# CarGeoLogger.net
KiCad netlist of a schematic drawn in Altium Designer
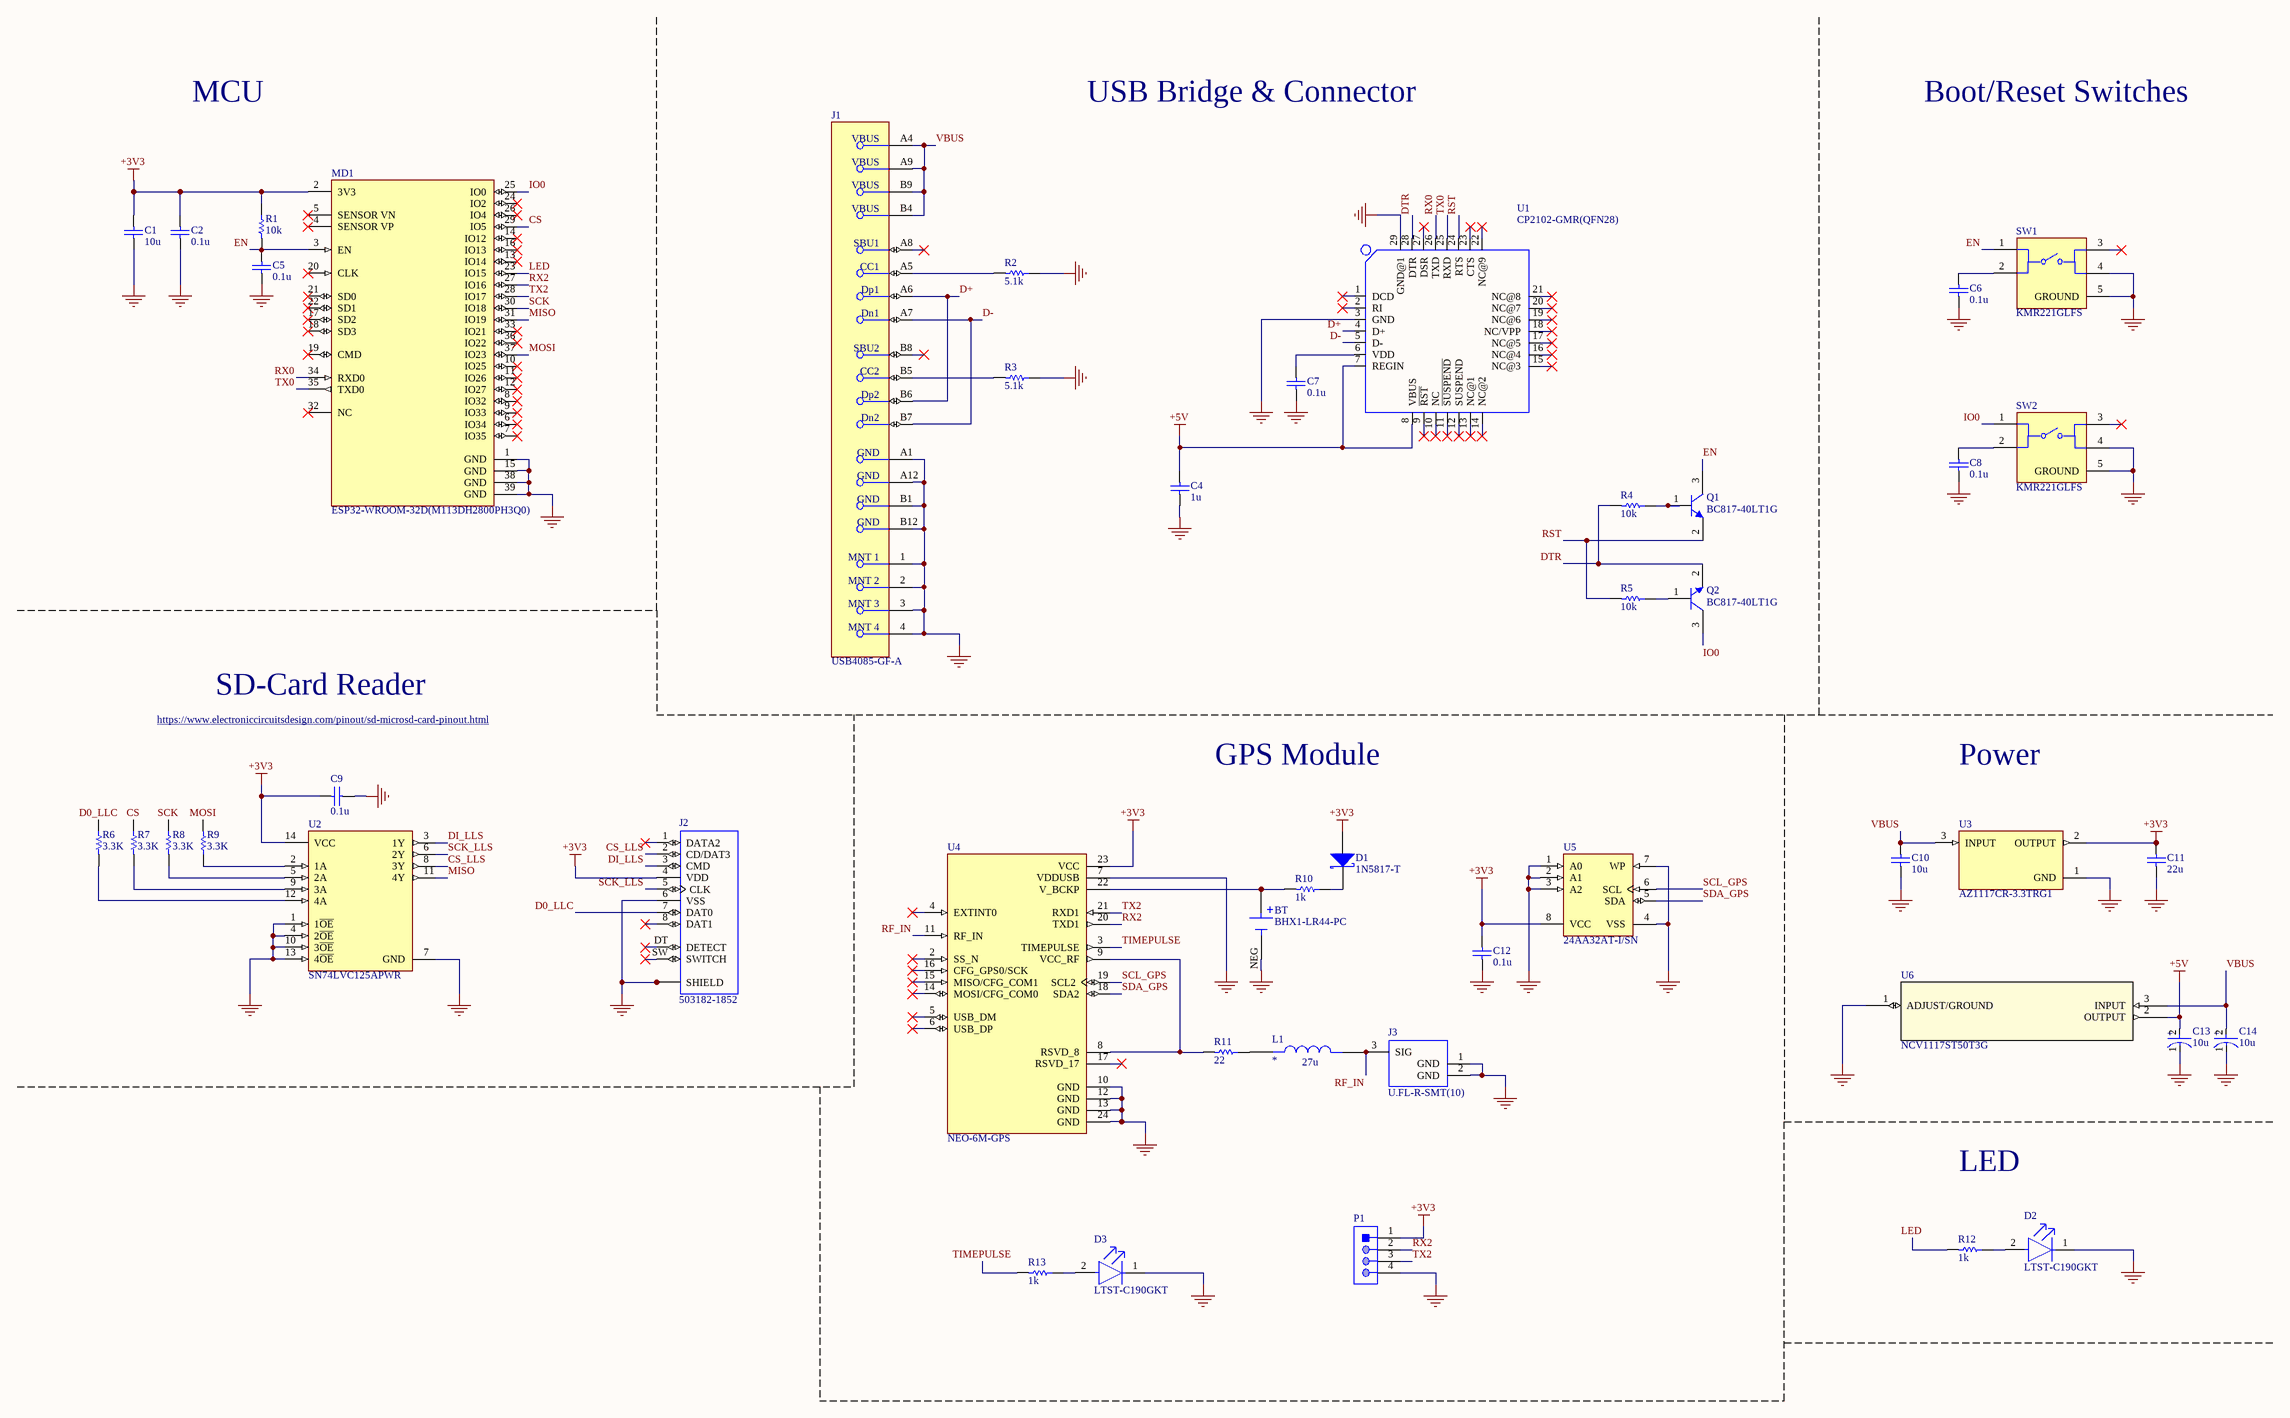
[diagram p0: CarGeoLogger.SchDoc]

(export (version "E")
  (design (tool "Eeschema 10.0.6"))
  (components
    (comp (ref "BT")
      (value "BHX1-LR44-PC")
      (footprint "BAT_BHX1-LR44-PC")
      (description "Battery Retainer Coin, 12.0mm 1 Cell PC Pin")
      (fields (field (name "MF") "MPD"))
      (libsource (lib "Kendrick Nguyen") (part "BHX1-LR44-PC"))
    )
    (comp (ref "C1")
      (value "10u")
      (footprint "CAPC1608X90X35ML10T15")
      (description "Chip Capacitor, 0603 (1608 Metric)")
      (fields (field (name "MANUFACTURER") "Murata"))
      (libsource (lib "Altium Content Vault") (part "CAP-NP-2"))
    )
    (comp (ref "C2")
      (value "0.1u")
      (footprint "CAPC1608X90X35ML10T15")
      (description "Chip Capacitor, 0603 (1608 Metric)")
      (fields (field (name "MANUFACTURER") "Murata"))
      (libsource (lib "Altium Content Vault") (part "CAP-NP-2"))
    )
    (comp (ref "C4")
      (value "1u")
      (footprint "CAPC1608X90X35ML10T15")
      (description "Chip Capacitor, 0603 (1608 Metric)")
      (fields (field (name "MANUFACTURER") "Murata"))
      (libsource (lib "Altium Content Vault") (part "CAP-NP-2"))
    )
    (comp (ref "C5")
      (value "0.1u")
      (footprint "CAPC1608X90X35ML10T15")
      (description "Chip Capacitor, 0603 (1608 Metric)")
      (fields (field (name "MANUFACTURER") "Murata"))
      (libsource (lib "Altium Content Vault") (part "CAP-NP-2"))
    )
    (comp (ref "C6")
      (value "0.1u")
      (footprint "CAPC1608X90X35ML10T15")
      (description "Chip Capacitor, 0603 (1608 Metric)")
      (fields (field (name "MANUFACTURER") "Murata"))
      (libsource (lib "Altium Content Vault") (part "CAP-NP-2"))
    )
    (comp (ref "C7")
      (value "0.1u")
      (footprint "CAPC1608X90X35ML10T15")
      (description "Chip Capacitor, 0603 (1608 Metric)")
      (fields (field (name "MANUFACTURER") "Murata"))
      (libsource (lib "Altium Content Vault") (part "CAP-NP-2"))
    )
    (comp (ref "C8")
      (value "0.1u")
      (footprint "CAPC1608X90X35ML10T15")
      (description "Chip Capacitor, 0603 (1608 Metric)")
      (fields (field (name "MANUFACTURER") "Murata"))
      (libsource (lib "Altium Content Vault") (part "CAP-NP-2"))
    )
    (comp (ref "C9")
      (value "0.1u")
      (footprint "CAPC1608X90X35ML10T15")
      (description "Chip Capacitor, 0603 (1608 Metric)")
      (fields (field (name "MANUFACTURER") "Murata"))
      (libsource (lib "Altium Content Vault") (part "CAP-NP-2"))
    )
    (comp (ref "C10")
      (value "10u")
      (footprint "CAPC1608X90X35ML10T15")
      (description "Chip Capacitor, 0603 (1608 Metric)")
      (fields (field (name "MANUFACTURER") "Murata"))
      (libsource (lib "Altium Content Vault") (part "CAP-NP-2"))
    )
    (comp (ref "C11")
      (value "22u")
      (footprint "CAPC1608X90X35ML10T15")
      (description "Chip Capacitor, 0603 (1608 Metric), F381A106MMAAH1")
      (fields (field (name "MANUFACTURER") "Murata"))
      (libsource (lib "Altium Content Vault") (part "CAP-NP-2"))
    )
    (comp (ref "C12")
      (value "0.1u")
      (footprint "CAPC1608X90X35ML10T15")
      (description "Chip Capacitor, 0603 (1608 Metric)")
      (fields (field (name "MANUFACTURER") "Murata"))
      (libsource (lib "Altium Content Vault") (part "CAP-NP-2"))
    )
    (comp (ref "C13")
      (value "10u")
      (footprint "FP-F38M-MFG")
      (description "CAP TANT POLY 10UF 10V SMD")
      (fields
        (field (name "MANUFACTURER PART NUMBER") "F381A106MMAAH1")
        (field (name "OCTOPART") "https://octopart.com/f381a106mmaah1-avx-67040376")
      )
      (libsource (lib "Altium Content Vault") (part "cf48714ba7e38822c1575c7ec0b6d1f"))
    )
    (comp (ref "C14")
      (value "10u")
      (footprint "FP-F38M-MFG")
      (description "CAP TANT POLY 10UF 10V SMD")
      (fields
        (field (name "MANUFACTURER PART NUMBER") "F381A106MMAAH1")
        (field (name "OCTOPART") "https://octopart.com/f381a106mmaah1-avx-67040376")
      )
      (libsource (lib "Altium Content Vault") (part "cf48714ba7e38822c1575c7ec0b6d1f"))
    )
    (comp (ref "D1")
      (value "1N5817-T")
      (footprint "DIOD-DO-41-P-2")
      (description "Schottky Barrier Rectifier, 1 A, 20 V, -65 to 125 degC, 2-Pin DO-41, RoHS, Tape and Reel")
      (fields (field (name "MANUFACTURER") "DiodesIncorporated"))
      (libsource (lib "Altium Content Vault") (part "DSKY-AK-2"))
    )
    (comp (ref "D2")
      (value "LTST-C190GKT")
      (footprint "FP-LTST-C190GKT-MFG")
      (description "LED GREEN CLEAR CHIP SMD")
      (fields (field (name "VOLTAGE") "2V"))
      (libsource (lib "Altium Content Vault") (part "8706943c75ba83719d021d2fdc84c58"))
    )
    (comp (ref "D3")
      (value "LTST-C190GKT")
      (footprint "FP-LTST-C190GKT-MFG")
      (description "LED GREEN CLEAR CHIP SMD")
      (fields (field (name "VOLTAGE") "2V"))
      (libsource (lib "Altium Content Vault") (part "8706943c75ba83719d021d2fdc84c58"))
    )
    (comp (ref "J1")
      (value "USB4085-GF-A")
      (footprint "FP-USB4085-GF-A-MFG")
      (description "CONN RCPT USB2.0 TYPE C 24POS RA")
      (libsource (lib "Altium Content Vault") (part "10fa745527c8b974685cbca3c197132"))
    )
    (comp (ref "J2")
      (value "503182-1852")
      (footprint "MOLEX_503182-1852")
      (description "Conn Micro SD Card M 8 POS 1.09mm Solder RA SMD Embossed T/R 0.5A/Contact")
      (libsource (lib "Kendrick Nguyen") (part "503182-1852"))
    )
    (comp (ref "J3")
      (value "U.FL-R-SMT(10)")
      (footprint "HRS-U.FL-R-SMT_V")
      (fields (field (name "MANUFACTURER") "Hirose Electric"))
      (libsource (lib "Kendrick Nguyen") (part "HRS-U.FL-R-SMT-3"))
    )
    (comp (ref "L1")
      (value "27u")
      (footprint "INDC1608X95N")
      (description "Ind RF Chip Shielded Multi-Layer 27uH 10% 1MHz 20Q-Factor Ferrite 2mA 0603 Punched Paper T/R")
      (fields
        (field (name "ALTIUM_VALUE") "*")
        (field (name "MF") "TDK")
        (field (name "MP") "MLF1608C270KTD00")
      )
      (libsource (lib "Kendrick Nguyen") (part "MLF1608C270KTD00"))
    )
    (comp (ref "MD1")
      (value "ESP32-WROOM-32D(M113DH2800PH3Q0)")
      (footprint "FP-ESP32-WROOM-32D_M113DH-MFG")
      (description "RX TXRX MOD WIFI TRACE ANT SMD")
      (libsource (lib "Altium Content Vault") (part "68cda691c5ebc01e0f685e2e9d3fb9b"))
    )
    (comp (ref "P1")
      (value "~")
      (footprint "61300411121")
      (description "THT Vertical Pin Header WR-PHD, Pitch 2.54 mm, Single Row, 4 pins")
      (fields
        (field (name "MANUFACTURER") "Wurth Elektronik")
        (field (name "PART NUMBER") "61300411121")
        (field (name "PUBLISHER") "WurthElektronik")
      )
      (libsource (lib "Altium Content Vault") (part "WE-CN-1P-M-R4"))
    )
    (comp (ref "Q1")
      (value "BC817-40LT1G")
      (footprint "ONSC-SOT-23-3-318-08_V")
      (description "General Purpose Transistor, NPN Silicon, 3-Pin SOT-23, Pb-Free, Tape and Reel")
      (fields (field (name "MANUFACTURER") "On Semiconductor"))
      (libsource (lib "Altium Content Vault") (part "ONSC-NPN-B1E2C3-3"))
    )
    (comp (ref "Q2")
      (value "BC817-40LT1G")
      (footprint "ONSC-SOT-23-3-318-08_V")
      (description "General Purpose Transistor, NPN Silicon, 3-Pin SOT-23, Pb-Free, Tape and Reel")
      (fields (field (name "MANUFACTURER") "On Semiconductor"))
      (libsource (lib "Altium Content Vault") (part "ONSC-NPN-B1E2C3-3"))
    )
    (comp (ref "R1")
      (value "10k")
      (footprint "RESC1609X50X30NL8T20")
      (description "Chip Resistor, 0603 (1608 Metric)")
      (fields (field (name "MANUFACTURER") "Vishay Semiconductor"))
      (libsource (lib "Altium Content Vault") (part "RES-2"))
    )
    (comp (ref "R2")
      (value "5.1k")
      (footprint "RESC1609X50X30NL8T20")
      (description "Chip Resistor, 0603 (1608 Metric)")
      (fields (field (name "MANUFACTURER") "Vishay Semiconductor"))
      (libsource (lib "Altium Content Vault") (part "RES-2"))
    )
    (comp (ref "R3")
      (value "5.1k")
      (footprint "RESC1609X50X30NL8T20")
      (description "Chip Resistor, 0603 (1608 Metric)")
      (fields (field (name "MANUFACTURER") "Vishay Semiconductor"))
      (libsource (lib "Altium Content Vault") (part "RES-2"))
    )
    (comp (ref "R4")
      (value "10k")
      (footprint "RESC1609X50X30NL8T20")
      (description "Chip Resistor, 0603 (1608 Metric)")
      (fields (field (name "MANUFACTURER") "Vishay Semiconductor"))
      (libsource (lib "Altium Content Vault") (part "RES-2"))
    )
    (comp (ref "R5")
      (value "10k")
      (footprint "RESC1609X50X30NL8T20")
      (description "Chip Resistor, 0603 (1608 Metric)")
      (fields (field (name "MANUFACTURER") "Vishay Semiconductor"))
      (libsource (lib "Altium Content Vault") (part "RES-2"))
    )
    (comp (ref "R6")
      (value "3.3K")
      (footprint "RESC1609X50X30NL8T20")
      (description "Chip Resistor, 0603 (1608 Metric)")
      (fields (field (name "MANUFACTURER") "Vishay Semiconductor"))
      (libsource (lib "Altium Content Vault") (part "RES-2"))
    )
    (comp (ref "R7")
      (value "3.3K")
      (footprint "RESC1609X50X30NL8T20")
      (description "Chip Resistor, 0603 (1608 Metric)")
      (fields (field (name "MANUFACTURER") "Vishay Semiconductor"))
      (libsource (lib "Altium Content Vault") (part "RES-2"))
    )
    (comp (ref "R8")
      (value "3.3K")
      (footprint "RESC1609X50X30NL8T20")
      (description "Chip Resistor, 0603 (1608 Metric)")
      (fields (field (name "MANUFACTURER") "Vishay Semiconductor"))
      (libsource (lib "Altium Content Vault") (part "RES-2"))
    )
    (comp (ref "R9")
      (value "3.3K")
      (footprint "RESC1609X50X30NL8T20")
      (description "Chip Resistor, 0603 (1608 Metric)")
      (fields (field (name "MANUFACTURER") "Vishay Semiconductor"))
      (libsource (lib "Altium Content Vault") (part "RES-2"))
    )
    (comp (ref "R10")
      (value "1k")
      (footprint "RESC1609X50X30NL8T20")
      (description "Chip Resistor, 0603 (1608 Metric)")
      (fields (field (name "MANUFACTURER") "Vishay Semiconductor"))
      (libsource (lib "Altium Content Vault") (part "RES-2"))
    )
    (comp (ref "R11")
      (value "22")
      (footprint "RESC1609X50X30NL8T20")
      (description "Chip Resistor, 0603 (1608 Metric)")
      (fields (field (name "MANUFACTURER") "Vishay Semiconductor"))
      (libsource (lib "Altium Content Vault") (part "RES-2"))
    )
    (comp (ref "R12")
      (value "1k")
      (footprint "RESC1609X50X30NL8T20")
      (description "Chip Resistor, 0603 (1608 Metric)")
      (fields (field (name "MANUFACTURER") "Vishay Semiconductor"))
      (libsource (lib "Altium Content Vault") (part "RES-2"))
    )
    (comp (ref "R13")
      (value "1k")
      (footprint "RESC1609X50X30NL8T20")
      (description "Chip Resistor, 0603 (1608 Metric)")
      (fields (field (name "MANUFACTURER") "Vishay Semiconductor"))
      (libsource (lib "Altium Content Vault") (part "RES-2"))
    )
    (comp (ref "SW1")
      (value "KMR221GLFS")
      (footprint "FP-KMR221GLFS-MFG")
      (description "SWITCH TACTILE SPST-NO 0.05A 32V")
      (libsource (lib "Altium Content Vault") (part "067e1cfe0b8977aedbfee7786663f4c"))
    )
    (comp (ref "SW2")
      (value "KMR221GLFS")
      (footprint "FP-KMR221GLFS-MFG")
      (description "SWITCH TACTILE SPST-NO 0.05A 32V")
      (libsource (lib "Altium Content Vault") (part "067e1cfe0b8977aedbfee7786663f4c"))
    )
    (comp (ref "U1")
      (value "CP2102-GMR(QFN28)")
      (footprint "QFN28G_0.5-5X5MM")
      (description "USB Bridge, USB to UART USB 2.0 UART Interface 28-QFN _5x5_")
      (fields (field (name "MP") "CP2102-GMR") (field (name "MF") "Silicon"))
      (libsource (lib "Kendrick Nguyen") (part "INTERFACE-CP2102-GMR(QFN28)"))
    )
    (comp (ref "U2")
      (value "SN74LVC125APWR")
      (footprint "FP-PW0014A-IPC_B")
      (description "IC BUF NON-INVERT 3.6V 14TSSOP")
      (libsource (lib "Altium Content Vault") (part "0c185306b27c65c3e4a0d950f37c68a"))
    )
    (comp (ref "U3")
      (value "AZ1117CR-3.3TRG1")
      (footprint "FP-SOT89-MFG")
      (description "IC REG LINEAR 3.3V 800MA SOT89")
      (fields
        (field (name "OCTOPART") "https://octopart.com/az1117cr-3.3trg1-diodes+inc.-30954805")
        (field (name "MANUFACTURER") "Diodes Inc.")
      )
      (libsource (lib "Altium Content Vault") (part "80dc4d5e0c5bf011f486f511683fde3"))
    )
    (comp (ref "U4")
      (value "NEO-6M-GPS")
      (footprint "XCVR_NEO-6M-GPS")
      (description "SMD GPS Module")
      (libsource (lib "Kendrick Nguyen") (part "NEO-6M-GPS"))
    )
    (comp (ref "U5")
      (value "24AA32AT-I/SN")
      (footprint "SOIC-SN8_L")
      (description "32Kbit, 400kHz, 1.7V, I2C Serial EEPROM, 8-Pin SOIC 150mil, Industrial Temperature, Tape and Reel")
      (libsource (lib "Altium Content Vault") (part "MEM-SEEPROM-34AA02-IL8"))
    )
    (comp (ref "U6")
      (value "NCV1117ST50T3G")
      (footprint "SOT223-3_ONS")
      (description "No Description Available")
      (fields (field (name "COPYRIGHT") "Copyright (C) 2022 Ultra Librarian. All rights reserved."))
      (libsource (lib "Kendrick Nguyen") (part "NCV1117ST50T3G"))
    )
  )
  (nets
    (net (code "1") (name "+3V3") (class "Default")
      (node (ref "C1") (pin "2") (pinfunction "2_2") (pintype "passive"))
      (node (ref "C11") (pin "2") (pinfunction "2_2") (pintype "passive"))
      (node (ref "C12") (pin "2") (pinfunction "2_2") (pintype "passive"))
      (node (ref "C2") (pin "2") (pinfunction "2_2") (pintype "passive"))
      (node (ref "C9") (pin "2") (pinfunction "2_2") (pintype "passive"))
      (node (ref "D1") (pin "1") (pinfunction "A_1") (pintype "passive"))
      (node (ref "J2") (pin "4") (pinfunction "VDD_4") (pintype "power_in"))
      (node (ref "MD1") (pin "2") (pinfunction "3V3_2") (pintype "power_in"))
      (node (ref "P1") (pin "1") (pinfunction "1_1") (pintype "passive"))
      (node (ref "R1") (pin "1") (pinfunction "1_1") (pintype "passive"))
      (node (ref "U2") (pin "14") (pinfunction "VCC_14") (pintype "power_in"))
      (node (ref "U3") (pin "2") (pinfunction "OUTPUT_2") (pintype "output"))
      (node (ref "U4") (pin "23") (pinfunction "VCC_23") (pintype "power_in"))
      (node (ref "U5") (pin "8") (pinfunction "VCC_8") (pintype "power_in"))
    )
    (net (code "2") (name "+5V") (class "Default")
      (node (ref "C13") (pin "2") (pinfunction "A_2") (pintype "passive"))
      (node (ref "C4") (pin "2") (pinfunction "2_2") (pintype "passive"))
      (node (ref "U1") (pin "7") (pinfunction "REGIN_7") (pintype "bidirectional"))
      (node (ref "U1") (pin "8") (pinfunction "VBUS_8") (pintype "bidirectional"))
      (node (ref "U6") (pin "2") (pinfunction "OUTPUT_2") (pintype "output"))
    )
    (net (code "3") (name "/CS") (class "Default")
      (node (ref "MD1") (pin "29") (pinfunction "IO5_29") (pintype "bidirectional"))
      (node (ref "R7") (pin "1") (pinfunction "1_1") (pintype "passive"))
    )
    (net (code "4") (name "/CS_LLS") (class "Default")
      (node (ref "J2") (pin "2") (pinfunction "CD/DAT3_2") (pintype "bidirectional"))
      (node (ref "U2") (pin "8") (pinfunction "3Y_8") (pintype "output"))
    )
    (net (code "5") (name "/D+") (class "Default")
      (node (ref "J1") (pin "A6") (pinfunction "Dp1_A6") (pintype "bidirectional"))
      (node (ref "J1") (pin "B6") (pinfunction "Dp2_B6") (pintype "bidirectional"))
      (node (ref "U1") (pin "4") (pinfunction "D+_4") (pintype "bidirectional"))
    )
    (net (code "6") (name "/D-") (class "Default")
      (node (ref "J1") (pin "A7") (pinfunction "Dn1_A7") (pintype "bidirectional"))
      (node (ref "J1") (pin "B7") (pinfunction "Dn2_B7") (pintype "bidirectional"))
      (node (ref "U1") (pin "5") (pinfunction "D-_5") (pintype "bidirectional"))
    )
    (net (code "7") (name "/D0_LLC") (class "Default")
      (node (ref "J2") (pin "7") (pinfunction "DAT0_7") (pintype "bidirectional"))
      (node (ref "R6") (pin "1") (pinfunction "1_1") (pintype "passive"))
    )
    (net (code "8") (name "/DI_LLS") (class "Default")
      (node (ref "J2") (pin "3") (pinfunction "CMD_3") (pintype "bidirectional"))
      (node (ref "U2") (pin "3") (pinfunction "1Y_3") (pintype "output"))
    )
    (net (code "9") (name "/DTR") (class "Default")
      (node (ref "Q2") (pin "2") (pinfunction "E_2") (pintype "passive"))
      (node (ref "R4") (pin "2") (pinfunction "2_2") (pintype "passive"))
      (node (ref "U1") (pin "28") (pinfunction "DTR_28") (pintype "bidirectional"))
    )
    (net (code "10") (name "/EN") (class "Default")
      (node (ref "C5") (pin "2") (pinfunction "2_2") (pintype "passive"))
      (node (ref "MD1") (pin "3") (pinfunction "EN_3") (pintype "input"))
      (node (ref "Q1") (pin "3") (pinfunction "C_3") (pintype "passive"))
      (node (ref "R1") (pin "2") (pinfunction "2_2") (pintype "passive"))
      (node (ref "SW1") (pin "1") (pinfunction "1_1") (pintype "passive"))
    )
    (net (code "11") (name "/IO0") (class "Default")
      (node (ref "MD1") (pin "25") (pinfunction "IO0_25") (pintype "bidirectional"))
      (node (ref "Q2") (pin "3") (pinfunction "C_3") (pintype "passive"))
      (node (ref "SW2") (pin "1") (pinfunction "1_1") (pintype "passive"))
    )
    (net (code "12") (name "/LED") (class "Default")
      (node (ref "MD1") (pin "23") (pinfunction "IO15_23") (pintype "bidirectional"))
      (node (ref "R12") (pin "2") (pinfunction "2_2") (pintype "passive"))
    )
    (net (code "13") (name "/MISO") (class "Default")
      (node (ref "MD1") (pin "31") (pinfunction "IO19_31") (pintype "bidirectional"))
      (node (ref "U2") (pin "11") (pinfunction "4Y_11") (pintype "output"))
    )
    (net (code "14") (name "/MOSI") (class "Default")
      (node (ref "MD1") (pin "37") (pinfunction "IO23_37") (pintype "bidirectional"))
      (node (ref "R9") (pin "2") (pinfunction "2_2") (pintype "passive"))
    )
    (net (code "15") (name "/RF_IN") (class "Default")
      (node (ref "J3") (pin "3") (pinfunction "SIG_3") (pintype "passive"))
      (node (ref "L1") (pin "2") (pinfunction "2_2") (pintype "passive"))
      (node (ref "U4") (pin "11") (pinfunction "RF_IN_11") (pintype "input"))
    )
    (net (code "16") (name "/RST") (class "Default")
      (node (ref "Q1") (pin "2") (pinfunction "E_2") (pintype "passive"))
      (node (ref "R5") (pin "2") (pinfunction "2_2") (pintype "passive"))
      (node (ref "U1") (pin "24") (pinfunction "RTS_24") (pintype "bidirectional"))
    )
    (net (code "17") (name "/RX0") (class "Default")
      (node (ref "MD1") (pin "34") (pinfunction "RXD0_34") (pintype "input"))
      (node (ref "U1") (pin "26") (pinfunction "TXD_26") (pintype "bidirectional"))
    )
    (net (code "18") (name "/RX2") (class "Default")
      (node (ref "MD1") (pin "27") (pinfunction "IO16_27") (pintype "bidirectional"))
      (node (ref "P1") (pin "2") (pinfunction "2_2") (pintype "passive"))
      (node (ref "U4") (pin "20") (pinfunction "TXD1_20") (pintype "output"))
    )
    (net (code "19") (name "/SCK") (class "Default")
      (node (ref "MD1") (pin "30") (pinfunction "IO18_30") (pintype "bidirectional"))
      (node (ref "R8") (pin "1") (pinfunction "1_1") (pintype "passive"))
    )
    (net (code "20") (name "/SCK_LLS") (class "Default")
      (node (ref "J2") (pin "5") (pinfunction "CLK_5") (pintype "bidirectional"))
      (node (ref "U2") (pin "6") (pinfunction "2Y_6") (pintype "output"))
    )
    (net (code "21") (name "/SCL_GPS") (class "Default")
      (node (ref "U4") (pin "19") (pinfunction "SCL2_19") (pintype "bidirectional"))
      (node (ref "U5") (pin "6") (pinfunction "SCL_6") (pintype "input"))
    )
    (net (code "22") (name "/SDA_GPS") (class "Default")
      (node (ref "U4") (pin "18") (pinfunction "SDA2_18") (pintype "bidirectional"))
      (node (ref "U5") (pin "5") (pinfunction "SDA_5") (pintype "bidirectional"))
    )
    (net (code "23") (name "/TIMEPULSE") (class "Default")
      (node (ref "R13") (pin "2") (pinfunction "2_2") (pintype "passive"))
      (node (ref "U4") (pin "3") (pinfunction "TIMEPULSE_3") (pintype "output"))
    )
    (net (code "24") (name "/TX0") (class "Default")
      (node (ref "MD1") (pin "35") (pinfunction "TXD0_35") (pintype "output"))
      (node (ref "U1") (pin "25") (pinfunction "RXD_25") (pintype "bidirectional"))
    )
    (net (code "25") (name "/TX2") (class "Default")
      (node (ref "MD1") (pin "28") (pinfunction "IO17_28") (pintype "bidirectional"))
      (node (ref "P1") (pin "3") (pinfunction "3_3") (pintype "passive"))
      (node (ref "U4") (pin "21") (pinfunction "RXD1_21") (pintype "input"))
    )
    (net (code "26") (name "/VBUS") (class "Default")
      (node (ref "C10") (pin "2") (pinfunction "2_2") (pintype "passive"))
      (node (ref "C14") (pin "2") (pinfunction "A_2") (pintype "passive"))
      (node (ref "J1") (pin "A4") (pinfunction "VBUS_A4") (pintype "power_in"))
      (node (ref "J1") (pin "A9") (pinfunction "VBUS_A9") (pintype "power_in"))
      (node (ref "J1") (pin "B4") (pinfunction "VBUS_B4") (pintype "power_in"))
      (node (ref "J1") (pin "B9") (pinfunction "VBUS_B9") (pintype "power_in"))
      (node (ref "U3") (pin "3") (pinfunction "INPUT_3") (pintype "input"))
      (node (ref "U6") (pin "3") (pinfunction "INPUT_3") (pintype "input"))
    )
    (net (code "27") (name "<NO NET>") (class "Default")
      (node (ref "BT") (pin "NEG") (pinfunction "NEG_NEG") (pintype "passive"))
      (node (ref "C1") (pin "1") (pinfunction "1_1") (pintype "passive"))
      (node (ref "C10") (pin "1") (pinfunction "1_1") (pintype "passive"))
      (node (ref "C11") (pin "1") (pinfunction "1_1") (pintype "passive"))
      (node (ref "C12") (pin "1") (pinfunction "1_1") (pintype "passive"))
      (node (ref "C13") (pin "1") (pinfunction "C_1") (pintype "passive"))
      (node (ref "C14") (pin "1") (pinfunction "C_1") (pintype "passive"))
      (node (ref "C2") (pin "1") (pinfunction "1_1") (pintype "passive"))
      (node (ref "C4") (pin "1") (pinfunction "1_1") (pintype "passive"))
      (node (ref "C5") (pin "1") (pinfunction "1_1") (pintype "passive"))
      (node (ref "C6") (pin "1") (pinfunction "1_1") (pintype "passive"))
      (node (ref "C7") (pin "1") (pinfunction "1_1") (pintype "passive"))
      (node (ref "C8") (pin "1") (pinfunction "1_1") (pintype "passive"))
      (node (ref "C9") (pin "1") (pinfunction "1_1") (pintype "passive"))
      (node (ref "D2") (pin "1") (pinfunction "C_1") (pintype "passive"))
      (node (ref "D3") (pin "1") (pinfunction "C_1") (pintype "passive"))
      (node (ref "J1") (pin "1") (pinfunction "MNT_1_1") (pintype "passive"))
      (node (ref "J1") (pin "2") (pinfunction "MNT_2_2") (pintype "passive"))
      (node (ref "J1") (pin "3") (pinfunction "MNT_3_3") (pintype "passive"))
      (node (ref "J1") (pin "4") (pinfunction "MNT_4_4") (pintype "passive"))
      (node (ref "J1") (pin "A1") (pinfunction "GND_A1") (pintype "power_in"))
      (node (ref "J1") (pin "A12") (pinfunction "GND_A12") (pintype "power_in"))
      (node (ref "J1") (pin "B1") (pinfunction "GND_B1") (pintype "power_in"))
      (node (ref "J1") (pin "B12") (pinfunction "GND_B12") (pintype "power_in"))
      (node (ref "J2") (pin "6") (pinfunction "VSS_6") (pintype "power_in"))
      (node (ref "J2") (pin "P1") (pinfunction "SHIELD_P1") (pintype "passive"))
      (node (ref "J2") (pin "P2") (pinfunction "SHIELD_P2") (pintype "passive"))
      (node (ref "J2") (pin "P3") (pinfunction "SHIELD_P3") (pintype "passive"))
      (node (ref "J2") (pin "P4") (pinfunction "SHIELD_P4") (pintype "passive"))
      (node (ref "J2") (pin "P5") (pinfunction "SHIELD_P5") (pintype "passive"))
      (node (ref "J3") (pin "1") (pinfunction "GND_1") (pintype "power_in"))
      (node (ref "J3") (pin "2") (pinfunction "GND_2") (pintype "power_in"))
      (node (ref "MD1") (pin "1") (pinfunction "GND_1") (pintype "power_in"))
      (node (ref "MD1") (pin "15") (pinfunction "GND_15") (pintype "power_in"))
      (node (ref "MD1") (pin "38") (pinfunction "GND_38") (pintype "power_in"))
      (node (ref "MD1") (pin "39") (pinfunction "GND_39") (pintype "power_in"))
      (node (ref "P1") (pin "4") (pinfunction "4_4") (pintype "passive"))
      (node (ref "R2") (pin "1") (pinfunction "1_1") (pintype "passive"))
      (node (ref "R3") (pin "1") (pinfunction "1_1") (pintype "passive"))
      (node (ref "SW1") (pin "4") (pinfunction "4_4") (pintype "passive"))
      (node (ref "SW1") (pin "5") (pinfunction "GROUND_5") (pintype "power_in"))
      (node (ref "SW2") (pin "4") (pinfunction "4_4") (pintype "passive"))
      (node (ref "SW2") (pin "5") (pinfunction "GROUND_5") (pintype "power_in"))
      (node (ref "U1") (pin "29") (pinfunction "GND@1_29") (pintype "bidirectional"))
      (node (ref "U1") (pin "3") (pinfunction "GND_3") (pintype "bidirectional"))
      (node (ref "U2") (pin "1") (pinfunction "1~{OE}_1") (pintype "input"))
      (node (ref "U2") (pin "10") (pinfunction "3~{OE}_10") (pintype "input"))
      (node (ref "U2") (pin "13") (pinfunction "4~{OE}_13") (pintype "input"))
      (node (ref "U2") (pin "4") (pinfunction "2~{OE}_4") (pintype "input"))
      (node (ref "U2") (pin "7") (pinfunction "GND_7") (pintype "power_in"))
      (node (ref "U3") (pin "1") (pinfunction "GND_1") (pintype "power_in"))
      (node (ref "U4") (pin "10") (pinfunction "GND_10") (pintype "power_in"))
      (node (ref "U4") (pin "12") (pinfunction "GND_12") (pintype "power_in"))
      (node (ref "U4") (pin "13") (pinfunction "GND_13") (pintype "power_in"))
      (node (ref "U4") (pin "24") (pinfunction "GND_24") (pintype "power_in"))
      (node (ref "U4") (pin "7") (pinfunction "VDDUSB_7") (pintype "power_in"))
      (node (ref "U5") (pin "1") (pinfunction "A0_1") (pintype "input"))
      (node (ref "U5") (pin "2") (pinfunction "A1_2") (pintype "input"))
      (node (ref "U5") (pin "3") (pinfunction "A2_3") (pintype "input"))
      (node (ref "U5") (pin "4") (pinfunction "VSS_4") (pintype "power_in"))
      (node (ref "U5") (pin "7") (pinfunction "WP_7") (pintype "input"))
      (node (ref "U6") (pin "1") (pinfunction "ADJUST/GROUND_1") (pintype "bidirectional"))
    )
    (net (code "28") (name "Net-(C6-Pad2)") (class "Default")
      (node (ref "C6") (pin "2") (pinfunction "2_2") (pintype "passive"))
      (node (ref "SW1") (pin "2") (pinfunction "2_2") (pintype "passive"))
    )
    (net (code "29") (name "Net-(C8-Pad2)") (class "Default")
      (node (ref "C8") (pin "2") (pinfunction "2_2") (pintype "passive"))
      (node (ref "SW2") (pin "2") (pinfunction "2_2") (pintype "passive"))
    )
    (net (code "30") (name "Net-(D1-K)") (class "Default")
      (node (ref "D1") (pin "2") (pinfunction "K_2") (pintype "passive"))
      (node (ref "R10") (pin "1") (pinfunction "1_1") (pintype "passive"))
    )
    (net (code "31") (name "Net-(D2-A)") (class "Default")
      (node (ref "D2") (pin "2") (pinfunction "A_2") (pintype "passive"))
      (node (ref "R12") (pin "1") (pinfunction "1_1") (pintype "passive"))
    )
    (net (code "32") (name "Net-(D3-A)") (class "Default")
      (node (ref "D3") (pin "2") (pinfunction "A_2") (pintype "passive"))
      (node (ref "R13") (pin "1") (pinfunction "1_1") (pintype "passive"))
    )
    (net (code "33") (name "Net-(J1-CC1)") (class "Default")
      (node (ref "J1") (pin "A5") (pinfunction "CC1_A5") (pintype "bidirectional"))
      (node (ref "R2") (pin "2") (pinfunction "2_2") (pintype "passive"))
    )
    (net (code "34") (name "Net-(J1-CC2)") (class "Default")
      (node (ref "J1") (pin "B5") (pinfunction "CC2_B5") (pintype "bidirectional"))
      (node (ref "R3") (pin "2") (pinfunction "2_2") (pintype "passive"))
    )
    (net (code "35") (name "Net-(L1-Pad1)") (class "Default")
      (node (ref "L1") (pin "1") (pinfunction "1_1") (pintype "passive"))
      (node (ref "R11") (pin "1") (pinfunction "1_1") (pintype "passive"))
    )
    (net (code "36") (name "Net-(Q1-B)") (class "Default")
      (node (ref "Q1") (pin "1") (pinfunction "B_1") (pintype "passive"))
      (node (ref "R4") (pin "1") (pinfunction "1_1") (pintype "passive"))
    )
    (net (code "37") (name "Net-(Q2-B)") (class "Default")
      (node (ref "Q2") (pin "1") (pinfunction "B_1") (pintype "passive"))
      (node (ref "R5") (pin "1") (pinfunction "1_1") (pintype "passive"))
    )
    (net (code "38") (name "Net-(U1-VDD)") (class "Default")
      (node (ref "C7") (pin "2") (pinfunction "2_2") (pintype "passive"))
      (node (ref "U1") (pin "6") (pinfunction "VDD_6") (pintype "bidirectional"))
    )
    (net (code "39") (name "Net-(U2-1A)") (class "Default")
      (node (ref "R9") (pin "1") (pinfunction "1_1") (pintype "passive"))
      (node (ref "U2") (pin "2") (pinfunction "1A_2") (pintype "input"))
    )
    (net (code "40") (name "Net-(U2-2A)") (class "Default")
      (node (ref "R8") (pin "2") (pinfunction "2_2") (pintype "passive"))
      (node (ref "U2") (pin "5") (pinfunction "2A_5") (pintype "input"))
    )
    (net (code "41") (name "Net-(U2-3A)") (class "Default")
      (node (ref "R7") (pin "2") (pinfunction "2_2") (pintype "passive"))
      (node (ref "U2") (pin "9") (pinfunction "3A_9") (pintype "input"))
    )
    (net (code "42") (name "Net-(U2-4A)") (class "Default")
      (node (ref "R6") (pin "2") (pinfunction "2_2") (pintype "passive"))
      (node (ref "U2") (pin "12") (pinfunction "4A_12") (pintype "input"))
    )
    (net (code "43") (name "Net-(U4-RSVD_8)") (class "Default")
      (node (ref "R11") (pin "2") (pinfunction "2_2") (pintype "passive"))
      (node (ref "U4") (pin "8") (pinfunction "RSVD_8_8") (pintype "passive"))
      (node (ref "U4") (pin "9") (pinfunction "VCC_RF_9") (pintype "output"))
    )
    (net (code "44") (name "Net-(U4-V_BCKP)") (class "Default")
      (node (ref "BT") (pin "1+") (pinfunction "POS_1+") (pintype "passive"))
      (node (ref "BT") (pin "2+") (pinfunction "POS_2+") (pintype "passive"))
      (node (ref "R10") (pin "2") (pinfunction "2_2") (pintype "passive"))
      (node (ref "U4") (pin "22") (pinfunction "V_BCKP_22") (pintype "power_in"))
    )
    (net (code "45") (name "unconnected-(J1-SBU1-PadA8)") (class "Default")
      (node (ref "J1") (pin "A8") (pinfunction "SBU1_A8") (pintype "bidirectional+no_connect"))
    )
    (net (code "46") (name "unconnected-(J1-SBU2-PadB8)") (class "Default")
      (node (ref "J1") (pin "B8") (pinfunction "SBU2_B8") (pintype "bidirectional+no_connect"))
    )
    (net (code "47") (name "unconnected-(J2-DAT1-Pad8)") (class "Default")
      (node (ref "J2") (pin "8") (pinfunction "DAT1_8") (pintype "bidirectional+no_connect"))
    )
    (net (code "48") (name "unconnected-(J2-DATA2-Pad1)") (class "Default")
      (node (ref "J2") (pin "1") (pinfunction "DATA2_1") (pintype "bidirectional+no_connect"))
    )
    (net (code "49") (name "unconnected-(J2-DETECT-PadDT)") (class "Default")
      (node (ref "J2") (pin "DT") (pinfunction "DETECT_DT") (pintype "bidirectional+no_connect"))
    )
    (net (code "50") (name "unconnected-(J2-SWITCH-PadSW)") (class "Default")
      (node (ref "J2") (pin "SW") (pinfunction "SWITCH_SW") (pintype "bidirectional+no_connect"))
    )
    (net (code "51") (name "unconnected-(MD1-CLK-Pad20)") (class "Default")
      (node (ref "MD1") (pin "20") (pinfunction "CLK_20") (pintype "input+no_connect"))
    )
    (net (code "52") (name "unconnected-(MD1-CMD-Pad19)") (class "Default")
      (node (ref "MD1") (pin "19") (pinfunction "CMD_19") (pintype "bidirectional+no_connect"))
    )
    (net (code "53") (name "unconnected-(MD1-IO2-Pad24)") (class "Default")
      (node (ref "MD1") (pin "24") (pinfunction "IO2_24") (pintype "bidirectional+no_connect"))
    )
    (net (code "54") (name "unconnected-(MD1-IO4-Pad26)") (class "Default")
      (node (ref "MD1") (pin "26") (pinfunction "IO4_26") (pintype "bidirectional+no_connect"))
    )
    (net (code "55") (name "unconnected-(MD1-IO12-Pad14)") (class "Default")
      (node (ref "MD1") (pin "14") (pinfunction "IO12_14") (pintype "bidirectional+no_connect"))
    )
    (net (code "56") (name "unconnected-(MD1-IO13-Pad16)") (class "Default")
      (node (ref "MD1") (pin "16") (pinfunction "IO13_16") (pintype "bidirectional+no_connect"))
    )
    (net (code "57") (name "unconnected-(MD1-IO14-Pad13)") (class "Default")
      (node (ref "MD1") (pin "13") (pinfunction "IO14_13") (pintype "bidirectional+no_connect"))
    )
    (net (code "58") (name "unconnected-(MD1-IO21-Pad33)") (class "Default")
      (node (ref "MD1") (pin "33") (pinfunction "IO21_33") (pintype "bidirectional+no_connect"))
    )
    (net (code "59") (name "unconnected-(MD1-IO22-Pad36)") (class "Default")
      (node (ref "MD1") (pin "36") (pinfunction "IO22_36") (pintype "bidirectional+no_connect"))
    )
    (net (code "60") (name "unconnected-(MD1-IO25-Pad10)") (class "Default")
      (node (ref "MD1") (pin "10") (pinfunction "IO25_10") (pintype "bidirectional+no_connect"))
    )
    (net (code "61") (name "unconnected-(MD1-IO26-Pad11)") (class "Default")
      (node (ref "MD1") (pin "11") (pinfunction "IO26_11") (pintype "bidirectional+no_connect"))
    )
    (net (code "62") (name "unconnected-(MD1-IO27-Pad12)") (class "Default")
      (node (ref "MD1") (pin "12") (pinfunction "IO27_12") (pintype "bidirectional+no_connect"))
    )
    (net (code "63") (name "unconnected-(MD1-IO32-Pad8)") (class "Default")
      (node (ref "MD1") (pin "8") (pinfunction "IO32_8") (pintype "bidirectional+no_connect"))
    )
    (net (code "64") (name "unconnected-(MD1-IO33-Pad9)") (class "Default")
      (node (ref "MD1") (pin "9") (pinfunction "IO33_9") (pintype "bidirectional+no_connect"))
    )
    (net (code "65") (name "unconnected-(MD1-IO34-Pad6)") (class "Default")
      (node (ref "MD1") (pin "6") (pinfunction "IO34_6") (pintype "bidirectional+no_connect"))
    )
    (net (code "66") (name "unconnected-(MD1-IO35-Pad7)") (class "Default")
      (node (ref "MD1") (pin "7") (pinfunction "IO35_7") (pintype "bidirectional+no_connect"))
    )
    (net (code "67") (name "unconnected-(MD1-NC-Pad32)") (class "Default")
      (node (ref "MD1") (pin "32") (pinfunction "NC_32") (pintype "passive+no_connect"))
    )
    (net (code "68") (name "unconnected-(MD1-SD0-Pad21)") (class "Default")
      (node (ref "MD1") (pin "21") (pinfunction "SD0_21") (pintype "bidirectional+no_connect"))
    )
    (net (code "69") (name "unconnected-(MD1-SD1-Pad22)") (class "Default")
      (node (ref "MD1") (pin "22") (pinfunction "SD1_22") (pintype "bidirectional+no_connect"))
    )
    (net (code "70") (name "unconnected-(MD1-SD2-Pad17)") (class "Default")
      (node (ref "MD1") (pin "17") (pinfunction "SD2_17") (pintype "bidirectional+no_connect"))
    )
    (net (code "71") (name "unconnected-(MD1-SD3-Pad18)") (class "Default")
      (node (ref "MD1") (pin "18") (pinfunction "SD3_18") (pintype "bidirectional+no_connect"))
    )
    (net (code "72") (name "unconnected-(MD1-SENSOR_VN-Pad5)") (class "Default")
      (node (ref "MD1") (pin "5") (pinfunction "SENSOR_VN_5") (pintype "passive+no_connect"))
    )
    (net (code "73") (name "unconnected-(MD1-SENSOR_VP-Pad4)") (class "Default")
      (node (ref "MD1") (pin "4") (pinfunction "SENSOR_VP_4") (pintype "passive+no_connect"))
    )
    (net (code "74") (name "unconnected-(SW1-Pad3)") (class "Default")
      (node (ref "SW1") (pin "3") (pinfunction "3_3") (pintype "passive+no_connect"))
    )
    (net (code "75") (name "unconnected-(SW2-Pad3)") (class "Default")
      (node (ref "SW2") (pin "3") (pinfunction "3_3") (pintype "passive+no_connect"))
    )
    (net (code "76") (name "unconnected-(U1-CTS-Pad23)") (class "Default")
      (node (ref "U1") (pin "23") (pinfunction "CTS_23") (pintype "bidirectional+no_connect"))
    )
    (net (code "77") (name "unconnected-(U1-DCD-Pad1)") (class "Default")
      (node (ref "U1") (pin "1") (pinfunction "DCD_1") (pintype "bidirectional+no_connect"))
    )
    (net (code "78") (name "unconnected-(U1-DSR-Pad27)") (class "Default")
      (node (ref "U1") (pin "27") (pinfunction "DSR_27") (pintype "bidirectional+no_connect"))
    )
    (net (code "79") (name "unconnected-(U1-NC-Pad10)") (class "Default")
      (node (ref "U1") (pin "10") (pinfunction "NC_10") (pintype "bidirectional+no_connect"))
    )
    (net (code "80") (name "unconnected-(U1-NC@1-Pad13)") (class "Default")
      (node (ref "U1") (pin "13") (pinfunction "NC@1_13") (pintype "bidirectional+no_connect"))
    )
    (net (code "81") (name "unconnected-(U1-NC@2-Pad14)") (class "Default")
      (node (ref "U1") (pin "14") (pinfunction "NC@2_14") (pintype "bidirectional+no_connect"))
    )
    (net (code "82") (name "unconnected-(U1-NC@3-Pad15)") (class "Default")
      (node (ref "U1") (pin "15") (pinfunction "NC@3_15") (pintype "bidirectional+no_connect"))
    )
    (net (code "83") (name "unconnected-(U1-NC@4-Pad16)") (class "Default")
      (node (ref "U1") (pin "16") (pinfunction "NC@4_16") (pintype "bidirectional+no_connect"))
    )
    (net (code "84") (name "unconnected-(U1-NC@5-Pad17)") (class "Default")
      (node (ref "U1") (pin "17") (pinfunction "NC@5_17") (pintype "bidirectional+no_connect"))
    )
    (net (code "85") (name "unconnected-(U1-NC@6-Pad19)") (class "Default")
      (node (ref "U1") (pin "19") (pinfunction "NC@6_19") (pintype "bidirectional+no_connect"))
    )
    (net (code "86") (name "unconnected-(U1-NC@7-Pad20)") (class "Default")
      (node (ref "U1") (pin "20") (pinfunction "NC@7_20") (pintype "bidirectional+no_connect"))
    )
    (net (code "87") (name "unconnected-(U1-NC@8-Pad21)") (class "Default")
      (node (ref "U1") (pin "21") (pinfunction "NC@8_21") (pintype "bidirectional+no_connect"))
    )
    (net (code "88") (name "unconnected-(U1-NC@9-Pad22)") (class "Default")
      (node (ref "U1") (pin "22") (pinfunction "NC@9_22") (pintype "bidirectional+no_connect"))
    )
    (net (code "89") (name "unconnected-(U1-NC{slash}VPP-Pad18)") (class "Default")
      (node (ref "U1") (pin "18") (pinfunction "NC/VPP_18") (pintype "bidirectional+no_connect"))
    )
    (net (code "90") (name "unconnected-(U1-RI-Pad2)") (class "Default")
      (node (ref "U1") (pin "2") (pinfunction "RI_2") (pintype "bidirectional+no_connect"))
    )
    (net (code "91") (name "unconnected-(U1-SUSPEND-Pad12)") (class "Default")
      (node (ref "U1") (pin "12") (pinfunction "SUSPEND_12") (pintype "bidirectional+no_connect"))
    )
    (net (code "92") (name "unconnected-(U1-~{RST}-Pad9)") (class "Default")
      (node (ref "U1") (pin "9") (pinfunction "~{RST}_9") (pintype "bidirectional+no_connect"))
    )
    (net (code "93") (name "unconnected-(U1-~{SUSPEND}-Pad11)") (class "Default")
      (node (ref "U1") (pin "11") (pinfunction "~{SUSPEND}_11") (pintype "bidirectional+no_connect"))
    )
    (net (code "94") (name "unconnected-(U4-CFG_GPS0{slash}SCK-Pad16)") (class "Default")
      (node (ref "U4") (pin "16") (pinfunction "CFG_GPS0/SCK_16") (pintype "input+no_connect"))
    )
    (net (code "95") (name "unconnected-(U4-EXTINT0-Pad4)") (class "Default")
      (node (ref "U4") (pin "4") (pinfunction "EXTINT0_4") (pintype "input+no_connect"))
    )
    (net (code "96") (name "unconnected-(U4-MISO{slash}CFG_COM1-Pad15)") (class "Default")
      (node (ref "U4") (pin "15") (pinfunction "MISO/CFG_COM1_15") (pintype "input+no_connect"))
    )
    (net (code "97") (name "unconnected-(U4-MOSI{slash}CFG_COM0-Pad14)") (class "Default")
      (node (ref "U4") (pin "14") (pinfunction "MOSI/CFG_COM0_14") (pintype "bidirectional+no_connect"))
    )
    (net (code "98") (name "unconnected-(U4-RSVD_17-Pad17)") (class "Default")
      (node (ref "U4") (pin "17") (pinfunction "RSVD_17_17") (pintype "passive+no_connect"))
    )
    (net (code "99") (name "unconnected-(U4-SS_N-Pad2)") (class "Default")
      (node (ref "U4") (pin "2") (pinfunction "SS_N_2") (pintype "input+no_connect"))
    )
    (net (code "100") (name "unconnected-(U4-USB_DM-Pad5)") (class "Default")
      (node (ref "U4") (pin "5") (pinfunction "USB_DM_5") (pintype "bidirectional+no_connect"))
    )
    (net (code "101") (name "unconnected-(U4-USB_DP-Pad6)") (class "Default")
      (node (ref "U4") (pin "6") (pinfunction "USB_DP_6") (pintype "bidirectional+no_connect"))
    )
  )
)
